# Forward.net
KiCad netlist of a schematic drawn in Altium Designer
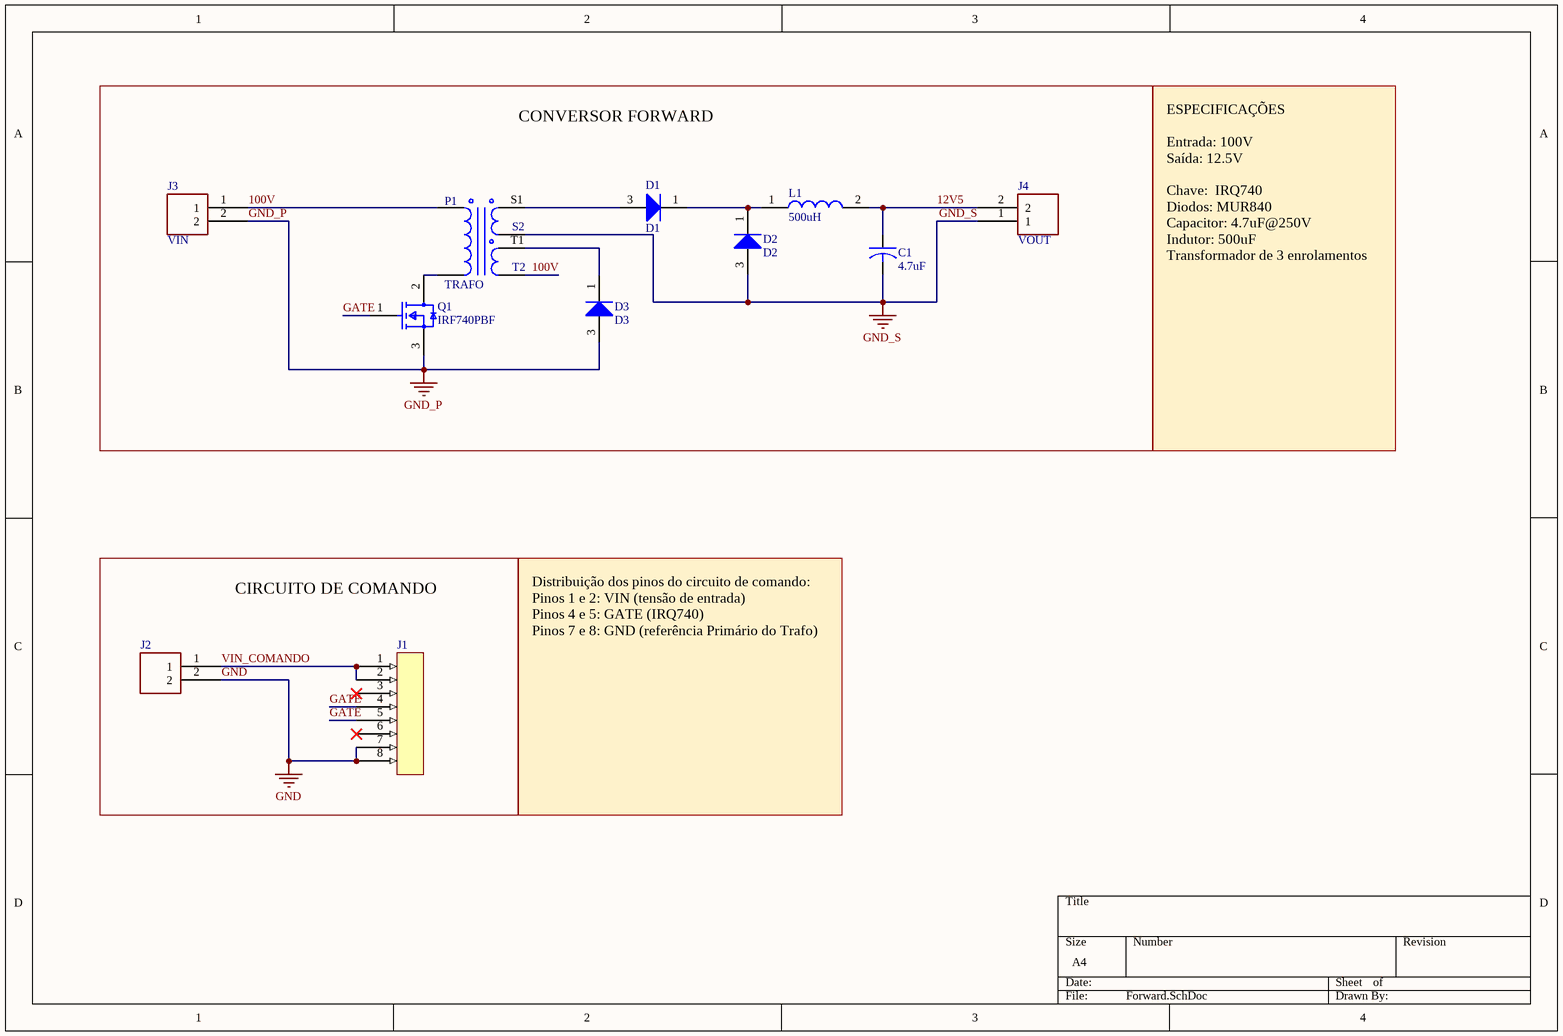
[diagram p0: Forward.SchDoc]

(export (version "E")
  (design (tool "Eeschema 10.0.6"))
  (components
    (comp (ref "C1")
      (value "4.7uF")
      (footprint "Capacitor")
      (libsource (lib "Elet_pot_2") (part "Capacitor Eletro"))
    )
    (comp (ref "D1") (value "D1") (footprint "MUR840") (libsource (lib "Elet_pot_2") (part "mur840")))
    (comp (ref "D2") (value "D2") (footprint "MUR840") (libsource (lib "Elet_pot_2") (part "mur840")))
    (comp (ref "D3") (value "D3") (footprint "MUR840") (libsource (lib "Elet_pot_2") (part "mur840")))
    (comp (ref "J1")
      (value "header 8pin")
      (footprint "Header 8pin")
      (libsource (lib "Elet_pot_2") (part "header 8pin"))
    )
    (comp (ref "J2")
      (value "Con_Molex_2_pin")
      (footprint "CON_MOLEX_2_vias")
      (libsource (lib "Elet_pot_2") (part "Con_Molex_2_pin"))
    )
    (comp (ref "J3")
      (value "VIN")
      (footprint "CON_MOLEX_2_vias")
      (libsource (lib "Elet_pot_2") (part "Con_Molex_2_pin"))
    )
    (comp (ref "J4")
      (value "VOUT")
      (footprint "Borne_KRE_2pin")
      (libsource (lib "Elet_pot_2") (part "Borne_KRE_2_vias"))
    )
    (comp (ref "L1") (value "500uH") (footprint "Indutor") (libsource (lib "Elet_pot_2") (part "Indutor")))
    (comp (ref "Q1")
      (value "IRF740PBF")
      (footprint "FP-X15-0364-MFG")
      (libsource (lib "Felipe Pastana") (part "b44c8776e10362b01251f5cff19d373"))
    )
    (comp (ref "TRAFO")
      (value "Trafo")
      (footprint "Trafo_NEE_30/14")
      (description "Transformador de 3 enrolamentos")
      (libsource (lib "Elet_pot_2") (part "Trafo"))
    )
  )
  (nets
    (net (code "1") (name "/12V5") (class "Default")
      (node (ref "C1") (pin "1") (pinfunction "1_1") (pintype "passive"))
      (node (ref "J4") (pin "2") (pinfunction "2_2") (pintype "passive"))
      (node (ref "L1") (pin "2") (pinfunction "2_2") (pintype "passive"))
    )
    (net (code "2") (name "/100V") (class "Default")
      (node (ref "J3") (pin "1") (pinfunction "1_1") (pintype "passive"))
      (node (ref "TRAFO") (pin "P1") (pinfunction "P1_P1") (pintype "passive"))
      (node (ref "TRAFO") (pin "S2") (pinfunction "S2_S2") (pintype "passive"))
    )
    (net (code "3") (name "/GATE") (class "Default")
      (node (ref "J1") (pin "4") (pinfunction "4_4") (pintype "input"))
      (node (ref "J1") (pin "5") (pinfunction "5_5") (pintype "input"))
      (node (ref "Q1") (pin "1") (pinfunction "G_1") (pintype "passive"))
    )
    (net (code "4") (name "/VIN_COMANDO") (class "Default")
      (node (ref "J1") (pin "1") (pinfunction "1_1") (pintype "input"))
      (node (ref "J1") (pin "2") (pinfunction "1_2") (pintype "input"))
      (node (ref "J2") (pin "1") (pinfunction "1_1") (pintype "passive"))
    )
    (net (code "5") (name "GND") (class "Default")
      (node (ref "J1") (pin "7") (pinfunction "7_7") (pintype "input"))
      (node (ref "J1") (pin "8") (pinfunction "8_8") (pintype "input"))
      (node (ref "J2") (pin "2") (pinfunction "2_2") (pintype "passive"))
    )
    (net (code "6") (name "GND_P") (class "Default")
      (node (ref "D3") (pin "3") (pinfunction "A_3") (pintype "passive"))
      (node (ref "J3") (pin "2") (pinfunction "2_2") (pintype "passive"))
      (node (ref "Q1") (pin "3") (pinfunction "S_3") (pintype "passive"))
    )
    (net (code "7") (name "GND_S") (class "Default")
      (node (ref "C1") (pin "2") (pinfunction "2_2") (pintype "passive"))
      (node (ref "D2") (pin "3") (pinfunction "A_3") (pintype "passive"))
      (node (ref "J4") (pin "1") (pinfunction "1_1") (pintype "passive"))
      (node (ref "TRAFO") (pin "S2") (pinfunction "S2_S2") (pintype "passive"))
    )
    (net (code "8") (name "Net-(D1-A)") (class "Default")
      (node (ref "D1") (pin "3") (pinfunction "A_3") (pintype "passive"))
      (node (ref "TRAFO") (pin "S1") (pinfunction "S1_S1") (pintype "passive"))
    )
    (net (code "9") (name "Net-(D1-K)") (class "Default")
      (node (ref "D1") (pin "1") (pinfunction "K_1") (pintype "passive"))
      (node (ref "D2") (pin "1") (pinfunction "K_1") (pintype "passive"))
      (node (ref "L1") (pin "1") (pinfunction "1_1") (pintype "passive"))
    )
    (net (code "10") (name "Net-(D3-K)") (class "Default")
      (node (ref "D3") (pin "1") (pinfunction "K_1") (pintype "passive"))
      (node (ref "TRAFO") (pin "T1") (pinfunction "T1_T1") (pintype "passive"))
    )
    (net (code "11") (name "Net-(Q1-D)") (class "Default")
      (node (ref "Q1") (pin "2") (pinfunction "D_2") (pintype "passive"))
      (node (ref "TRAFO") (pin "P2") (pinfunction "gg_P2") (pintype "passive"))
    )
    (net (code "12") (name "unconnected-(J1-Pad3)") (class "Default")
      (node (ref "J1") (pin "3") (pinfunction "3_3") (pintype "input+no_connect"))
    )
    (net (code "13") (name "unconnected-(J1-Pad6)") (class "Default")
      (node (ref "J1") (pin "6") (pinfunction "6_6") (pintype "input+no_connect"))
    )
  )
)
